# CartSimple.net
KiCad netlist of a schematic drawn in Altium Designer
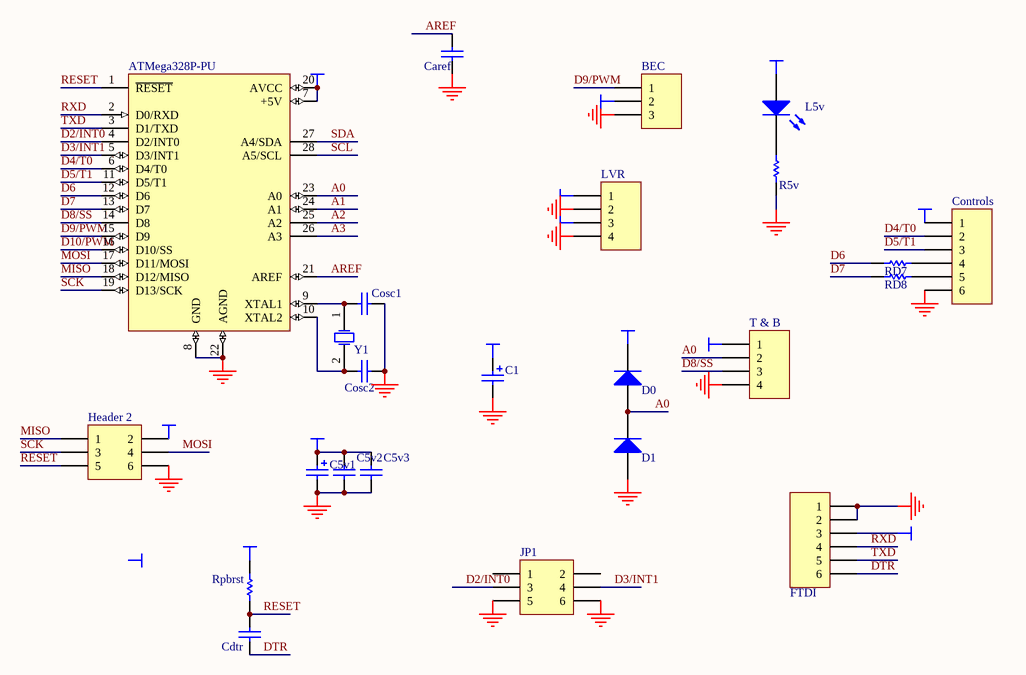
[diagram p0: CartSimple.SCHDOC]

(export (version "E")
  (design (tool "Eeschema 10.0.6"))
  (components
    (comp (ref "ATMega328P-PU")
      (value "Atmel ATMega328")
      (footprint "DIP 28")
      (description "EPROM-Based 8-Bit CMOS Microcontroller")
      (fields
        (field (name "MANUFACTURER") "Atmel")
        (field (name "PART NUMBER") "ATMega 328P-PU")
        (field (name "PUBLISHER") "Altium Limited")
      )
      (libsource (lib "Microchip Microcontroller 8-bit") (part "PIC16C55-10/SS"))
    )
    (comp (ref "BEC")
      (value "Header 3")
      (footprint "Header 3way 2.54")
      (description "Header, 3-Pin")
      (fields (field (name "MANUFACTURER") "Generic Components") (field (name "PUBLISHER") "Altium Limited"))
      (libsource (lib "Miscellaneous Connectors") (part "Header 3"))
    )
    (comp (ref "C1")
      (value "Cap Pol1")
      (footprint "Electrolytic Capacitor 8mm")
      (description "Polarized Capacitor (Radial)")
      (fields (field (name "MANUFACTURER") "Generic Components") (field (name "PUBLISHER") "Altium Limited"))
      (libsource (lib "Miscellaneous Devices") (part "Cap Pol1"))
    )
    (comp (ref "C5v1")
      (value "Cap Pol1")
      (footprint "Electrolytic Capacitor 8mm")
      (description "Polarized Capacitor (Radial)")
      (fields (field (name "MANUFACTURER") "Generic Components") (field (name "PUBLISHER") "Altium Limited"))
      (libsource (lib "Miscellaneous Devices") (part "Cap Pol1"))
    )
    (comp (ref "C5v2")
      (value "Cap")
      (footprint "Capacitor 5mm")
      (description "Capacitor")
      (fields (field (name "MANUFACTURER") "Generic Components") (field (name "PUBLISHER") "Altium Limited"))
      (libsource (lib "Miscellaneous Devices") (part "Cap"))
    )
    (comp (ref "C5v3")
      (value "Cap")
      (footprint "Capacitor 5mm")
      (description "Capacitor")
      (fields (field (name "MANUFACTURER") "Generic Components") (field (name "PUBLISHER") "Altium Limited"))
      (libsource (lib "Miscellaneous Devices") (part "Cap"))
    )
    (comp (ref "Caref")
      (value "Cap")
      (footprint "Capacitor 5mm")
      (description "Capacitor")
      (fields (field (name "MANUFACTURER") "Generic Components") (field (name "PUBLISHER") "Altium Limited"))
      (libsource (lib "Miscellaneous Devices") (part "Cap"))
    )
    (comp (ref "Cdtr")
      (value "Cap")
      (footprint "Capacitor 5mm")
      (description "Capacitor")
      (fields (field (name "MANUFACTURER") "Generic Components") (field (name "PUBLISHER") "Altium Limited"))
      (libsource (lib "Miscellaneous Devices") (part "Cap"))
    )
    (comp (ref "Controls")
      (value "Header 6")
      (footprint "Header 6way 2.54")
      (description "Header, 6-Pin")
      (fields (field (name "MANUFACTURER") "Generic Components") (field (name "PUBLISHER") "Altium Limited"))
      (libsource (lib "Miscellaneous Connectors") (part "Header 6"))
    )
    (comp (ref "Cosc1")
      (value "Cap")
      (footprint "Capacitor 5mm")
      (description "Capacitor")
      (fields (field (name "MANUFACTURER") "Generic Components") (field (name "PUBLISHER") "Altium Limited"))
      (libsource (lib "Miscellaneous Devices") (part "Cap"))
    )
    (comp (ref "Cosc2")
      (value "Cap")
      (footprint "Capacitor 5mm")
      (description "Capacitor")
      (fields (field (name "MANUFACTURER") "Generic Components") (field (name "PUBLISHER") "Altium Limited"))
      (libsource (lib "Miscellaneous Devices") (part "Cap"))
    )
    (comp (ref "D0")
      (value "Diode")
      (footprint "Signal Diode")
      (description "Default Diode")
      (fields (field (name "MANUFACTURER") "Generic Components") (field (name "PUBLISHER") "Altium Limited"))
      (libsource (lib "Miscellaneous Devices") (part "Diode"))
    )
    (comp (ref "D1")
      (value "Diode")
      (footprint "Signal Diode")
      (description "Default Diode")
      (fields (field (name "MANUFACTURER") "Generic Components") (field (name "PUBLISHER") "Altium Limited"))
      (libsource (lib "Miscellaneous Devices") (part "Diode"))
    )
    (comp (ref "FTDI")
      (value "Header 6")
      (footprint "Header 6")
      (description "Header, 6-Pin")
      (fields (field (name "MANUFACTURER") "Generic Components") (field (name "PUBLISHER") "Altium Limited"))
      (libsource (lib "") (part "Header 6_1"))
    )
    (comp (ref "Header 2")
      (value "Header 3X2")
      (footprint "Header 2x3")
      (description "Header, 3-Pin, Dual row")
      (fields (field (name "MANUFACTURER") "Generic Components") (field (name "PUBLISHER") "Altium Limited"))
      (libsource (lib "Miscellaneous Connectors") (part "Header 3X2"))
    )
    (comp (ref "JP1")
      (value "Header 3X2")
      (footprint "Header 2x3")
      (description "Header, 3-Pin, Dual row")
      (fields (field (name "MANUFACTURER") "Generic Components") (field (name "PUBLISHER") "Altium Limited"))
      (libsource (lib "Miscellaneous Connectors") (part "Header 3X2"))
    )
    (comp (ref "L5v")
      (value "LED0")
      (footprint "Led 3mm")
      (description "Typical INFRARED GaAs LED")
      (fields
        (field (name "MANUFACTURER") "Multicomp")
        (field (name "PART NUMBER") "OVL-3328")
        (field (name "PUBLISHER") "Altium Limited")
      )
      (libsource (lib "Miscellaneous Devices") (part "LED0"))
    )
    (comp (ref "LVR")
      (value "Header 4")
      (footprint "SOT-223")
      (description "Header, 4-Pin")
      (fields (field (name "MANUFACTURER") "Generic Components") (field (name "PUBLISHER") "Altium Limited"))
      (libsource (lib "Miscellaneous Connectors") (part "Header 4"))
    )
    (comp (ref "R5v")
      (value "Res1")
      (footprint "1/4W Resistor")
      (description "Resistor")
      (fields (field (name "MANUFACTURER") "Generic Components") (field (name "PUBLISHER") "Altium Limited"))
      (libsource (lib "Miscellaneous Devices") (part "Res1"))
    )
    (comp (ref "RD7")
      (value "Res1")
      (footprint "1/4W Resistor")
      (description "Resistor")
      (fields (field (name "MANUFACTURER") "Generic Components") (field (name "PUBLISHER") "Altium Limited"))
      (libsource (lib "Miscellaneous Devices") (part "Res1"))
    )
    (comp (ref "RD8")
      (value "Res1")
      (footprint "1/4W Resistor")
      (description "Resistor")
      (fields (field (name "MANUFACTURER") "Generic Components") (field (name "PUBLISHER") "Altium Limited"))
      (libsource (lib "Miscellaneous Devices") (part "Res1"))
    )
    (comp (ref "Rpbrst")
      (value "Res1")
      (footprint "1/4W Resistor")
      (description "Resistor")
      (fields (field (name "MANUFACTURER") "Generic Components") (field (name "PUBLISHER") "Altium Limited"))
      (libsource (lib "Miscellaneous Devices") (part "Res1"))
    )
    (comp (ref "T & B")
      (value "Header 4")
      (footprint "Header 4way 2.54")
      (description "Header, 4-Pin")
      (fields (field (name "MANUFACTURER") "Generic Components") (field (name "PUBLISHER") "Altium Limited"))
      (libsource (lib "Miscellaneous Connectors") (part "Header 4"))
    )
    (comp (ref "Y1")
      (value "16MHz XTAL")
      (footprint "Crystal")
      (description "Crystal Oscillator")
      (fields
        (field (name "MANUFACTURER") "Raltron")
        (field (name "PART NUMBER") "AS-16.000-18")
        (field (name "PUBLISHER") "Altium Limited")
      )
      (libsource (lib "Miscellaneous Devices") (part "XTAL"))
    )
  )
  (nets
    (net (code "1") (name "+5") (class "Default")
      (node (ref "ATMega328P-PU") (pin "20") (pinfunction "AVCC_20") (pintype "bidirectional"))
      (node (ref "ATMega328P-PU") (pin "7") (pinfunction "+5V_7") (pintype "bidirectional"))
      (node (ref "C5v1") (pin "1") (pinfunction "1_1") (pintype "passive"))
      (node (ref "C5v2") (pin "1") (pinfunction "1_1") (pintype "passive"))
      (node (ref "C5v3") (pin "1") (pinfunction "1_1") (pintype "passive"))
      (node (ref "Controls") (pin "1") (pinfunction "1_1") (pintype "passive"))
      (node (ref "D0") (pin "2") (pinfunction "K_2") (pintype "passive"))
      (node (ref "FTDI") (pin "3") (pinfunction "3_3") (pintype "passive"))
      (node (ref "Header 2") (pin "2") (pinfunction "2_2") (pintype "passive"))
      (node (ref "L5v") (pin "1") (pinfunction "A_1") (pintype "passive"))
      (node (ref "LVR") (pin "1") (pinfunction "1_1") (pintype "passive"))
      (node (ref "Rpbrst") (pin "2") (pinfunction "2_2") (pintype "passive"))
      (node (ref "T & B") (pin "1") (pinfunction "1_1") (pintype "passive"))
    )
    (net (code "2") (name "/A0") (class "Default")
      (node (ref "ATMega328P-PU") (pin "23") (pinfunction "A0_23") (pintype "bidirectional"))
      (node (ref "D0") (pin "1") (pinfunction "A_1") (pintype "passive"))
      (node (ref "D1") (pin "2") (pinfunction "K_2") (pintype "passive"))
      (node (ref "T & B") (pin "2") (pinfunction "2_2") (pintype "passive"))
    )
    (net (code "3") (name "/A1") (class "Default")
      (node (ref "ATMega328P-PU") (pin "24") (pinfunction "A1_24") (pintype "bidirectional"))
    )
    (net (code "4") (name "/A2") (class "Default")
      (node (ref "ATMega328P-PU") (pin "25") (pinfunction "A2_25") (pintype "passive"))
    )
    (net (code "5") (name "/A3") (class "Default")
      (node (ref "ATMega328P-PU") (pin "26") (pinfunction "A3_26") (pintype "passive"))
    )
    (net (code "6") (name "/AREF") (class "Default")
      (node (ref "ATMega328P-PU") (pin "21") (pinfunction "AREF_21") (pintype "bidirectional"))
      (node (ref "Caref") (pin "1") (pinfunction "1_1") (pintype "passive"))
    )
    (net (code "7") (name "/D2{slash}INT0") (class "Default")
      (node (ref "ATMega328P-PU") (pin "4") (pinfunction "D2/INT0_4") (pintype "power_in"))
      (node (ref "JP1") (pin "3") (pinfunction "3_3") (pintype "passive"))
    )
    (net (code "8") (name "/D3{slash}INT1") (class "Default")
      (node (ref "ATMega328P-PU") (pin "5") (pinfunction "D3/INT1_5") (pintype "bidirectional"))
      (node (ref "JP1") (pin "4") (pinfunction "4_4") (pintype "passive"))
    )
    (net (code "9") (name "/D4{slash}T0") (class "Default")
      (node (ref "ATMega328P-PU") (pin "6") (pinfunction "D4/T0_6") (pintype "bidirectional"))
      (node (ref "Controls") (pin "2") (pinfunction "2_2") (pintype "passive"))
    )
    (net (code "10") (name "/D5{slash}T1") (class "Default")
      (node (ref "ATMega328P-PU") (pin "11") (pinfunction "D5/T1_11") (pintype "bidirectional"))
      (node (ref "Controls") (pin "3") (pinfunction "3_3") (pintype "passive"))
    )
    (net (code "11") (name "/D6") (class "Default")
      (node (ref "ATMega328P-PU") (pin "12") (pinfunction "D6_12") (pintype "bidirectional"))
      (node (ref "RD7") (pin "2") (pinfunction "2_2") (pintype "passive"))
    )
    (net (code "12") (name "/D7") (class "Default")
      (node (ref "ATMega328P-PU") (pin "13") (pinfunction "D7_13") (pintype "bidirectional"))
      (node (ref "RD8") (pin "2") (pinfunction "2_2") (pintype "passive"))
    )
    (net (code "13") (name "/D8{slash}SS") (class "Default")
      (node (ref "ATMega328P-PU") (pin "14") (pinfunction "D8_14") (pintype "power_in"))
      (node (ref "T & B") (pin "3") (pinfunction "3_3") (pintype "passive"))
    )
    (net (code "14") (name "/D9{slash}PWM") (class "Default")
      (node (ref "ATMega328P-PU") (pin "15") (pinfunction "D9_15") (pintype "bidirectional"))
      (node (ref "BEC") (pin "1") (pinfunction "1_1") (pintype "passive"))
    )
    (net (code "15") (name "/D10{slash}PWM") (class "Default")
      (node (ref "ATMega328P-PU") (pin "16") (pinfunction "D10/SS_16") (pintype "bidirectional"))
    )
    (net (code "16") (name "/DTR") (class "Default")
      (node (ref "Cdtr") (pin "2") (pinfunction "2_2") (pintype "passive"))
      (node (ref "FTDI") (pin "6") (pinfunction "6_6") (pintype "passive"))
    )
    (net (code "17") (name "/MISO") (class "Default")
      (node (ref "ATMega328P-PU") (pin "18") (pinfunction "D12/MISO_18") (pintype "bidirectional"))
      (node (ref "Header 2") (pin "1") (pinfunction "1_1") (pintype "passive"))
    )
    (net (code "18") (name "/MOSI") (class "Default")
      (node (ref "ATMega328P-PU") (pin "17") (pinfunction "D11/MOSI_17") (pintype "bidirectional"))
      (node (ref "Header 2") (pin "4") (pinfunction "4_4") (pintype "passive"))
    )
    (net (code "19") (name "/RESET") (class "Default")
      (node (ref "ATMega328P-PU") (pin "1") (pinfunction "~{RESET}_1") (pintype "power_in"))
      (node (ref "Cdtr") (pin "1") (pinfunction "1_1") (pintype "passive"))
      (node (ref "Header 2") (pin "5") (pinfunction "5_5") (pintype "passive"))
      (node (ref "Rpbrst") (pin "1") (pinfunction "1_1") (pintype "passive"))
    )
    (net (code "20") (name "/RXD") (class "Default")
      (node (ref "ATMega328P-PU") (pin "2") (pinfunction "D0/RXD_2") (pintype "input"))
      (node (ref "FTDI") (pin "4") (pinfunction "4_4") (pintype "passive"))
    )
    (net (code "21") (name "/SCK") (class "Default")
      (node (ref "ATMega328P-PU") (pin "19") (pinfunction "D13/SCK_19") (pintype "bidirectional"))
      (node (ref "Header 2") (pin "3") (pinfunction "3_3") (pintype "passive"))
    )
    (net (code "22") (name "/SCL") (class "Default")
      (node (ref "ATMega328P-PU") (pin "28") (pinfunction "A5/SCL_28") (pintype "passive"))
    )
    (net (code "23") (name "/SDA") (class "Default")
      (node (ref "ATMega328P-PU") (pin "27") (pinfunction "A4/SDA_27") (pintype "passive"))
    )
    (net (code "24") (name "/TXD") (class "Default")
      (node (ref "ATMega328P-PU") (pin "3") (pinfunction "D1/TXD_3") (pintype "power_in"))
      (node (ref "FTDI") (pin "5") (pinfunction "5_5") (pintype "passive"))
    )
    (net (code "25") (name "GND") (class "Default")
      (node (ref "ATMega328P-PU") (pin "22") (pinfunction "AGND_22") (pintype "bidirectional"))
      (node (ref "ATMega328P-PU") (pin "8") (pinfunction "GND_8") (pintype "bidirectional"))
      (node (ref "BEC") (pin "3") (pinfunction "3_3") (pintype "passive"))
      (node (ref "C1") (pin "2") (pinfunction "2_2") (pintype "passive"))
      (node (ref "C5v1") (pin "2") (pinfunction "2_2") (pintype "passive"))
      (node (ref "C5v2") (pin "2") (pinfunction "2_2") (pintype "passive"))
      (node (ref "C5v3") (pin "2") (pinfunction "2_2") (pintype "passive"))
      (node (ref "Caref") (pin "2") (pinfunction "2_2") (pintype "passive"))
      (node (ref "Controls") (pin "6") (pinfunction "6_6") (pintype "passive"))
      (node (ref "Cosc1") (pin "2") (pinfunction "2_2") (pintype "passive"))
      (node (ref "Cosc2") (pin "2") (pinfunction "2_2") (pintype "passive"))
      (node (ref "D1") (pin "1") (pinfunction "A_1") (pintype "passive"))
      (node (ref "FTDI") (pin "1") (pinfunction "1_1") (pintype "passive"))
      (node (ref "FTDI") (pin "2") (pinfunction "2_2") (pintype "passive"))
      (node (ref "Header 2") (pin "6") (pinfunction "6_6") (pintype "passive"))
      (node (ref "JP1") (pin "5") (pinfunction "5_5") (pintype "passive"))
      (node (ref "JP1") (pin "6") (pinfunction "6_6") (pintype "passive"))
      (node (ref "LVR") (pin "2") (pinfunction "2_2") (pintype "passive"))
      (node (ref "LVR") (pin "4") (pinfunction "4_4") (pintype "passive"))
      (node (ref "R5v") (pin "1") (pinfunction "1_1") (pintype "passive"))
      (node (ref "T & B") (pin "4") (pinfunction "4_4") (pintype "passive"))
    )
    (net (code "26") (name "Net-(ATMega328P-PU-XTAL1)") (class "Default")
      (node (ref "ATMega328P-PU") (pin "9") (pinfunction "XTAL1_9") (pintype "bidirectional"))
      (node (ref "Cosc1") (pin "1") (pinfunction "1_1") (pintype "passive"))
      (node (ref "Y1") (pin "1") (pinfunction "OSC1_1") (pintype "passive"))
    )
    (net (code "27") (name "Net-(ATMega328P-PU-XTAL2)") (class "Default")
      (node (ref "ATMega328P-PU") (pin "10") (pinfunction "XTAL2_10") (pintype "bidirectional"))
      (node (ref "Cosc2") (pin "1") (pinfunction "1_1") (pintype "passive"))
      (node (ref "Y1") (pin "2") (pinfunction "OSC2_2") (pintype "passive"))
    )
    (net (code "28") (name "Net-(Controls-Pad4)") (class "Default")
      (node (ref "Controls") (pin "4") (pinfunction "4_4") (pintype "passive"))
      (node (ref "RD7") (pin "1") (pinfunction "1_1") (pintype "passive"))
    )
    (net (code "29") (name "Net-(Controls-Pad5)") (class "Default")
      (node (ref "Controls") (pin "5") (pinfunction "5_5") (pintype "passive"))
      (node (ref "RD8") (pin "1") (pinfunction "1_1") (pintype "passive"))
    )
    (net (code "30") (name "Net-(L5v-K)") (class "Default")
      (node (ref "L5v") (pin "2") (pinfunction "K_2") (pintype "passive"))
      (node (ref "R5v") (pin "2") (pinfunction "2_2") (pintype "passive"))
    )
    (net (code "31") (name "VCC") (class "Default")
      (node (ref "BEC") (pin "2") (pinfunction "2_2") (pintype "passive"))
      (node (ref "C1") (pin "1") (pinfunction "1_1") (pintype "passive"))
      (node (ref "LVR") (pin "3") (pinfunction "3_3") (pintype "passive"))
    )
    (net (code "32") (name "unconnected-(JP1-Pad1)") (class "Default")
      (node (ref "JP1") (pin "1") (pinfunction "1_1") (pintype "passive"))
    )
    (net (code "33") (name "unconnected-(JP1-Pad2)") (class "Default")
      (node (ref "JP1") (pin "2") (pinfunction "2_2") (pintype "passive"))
    )
  )
)
